# FrontEndEval.net
KiCad netlist of a schematic drawn in Altium Designer
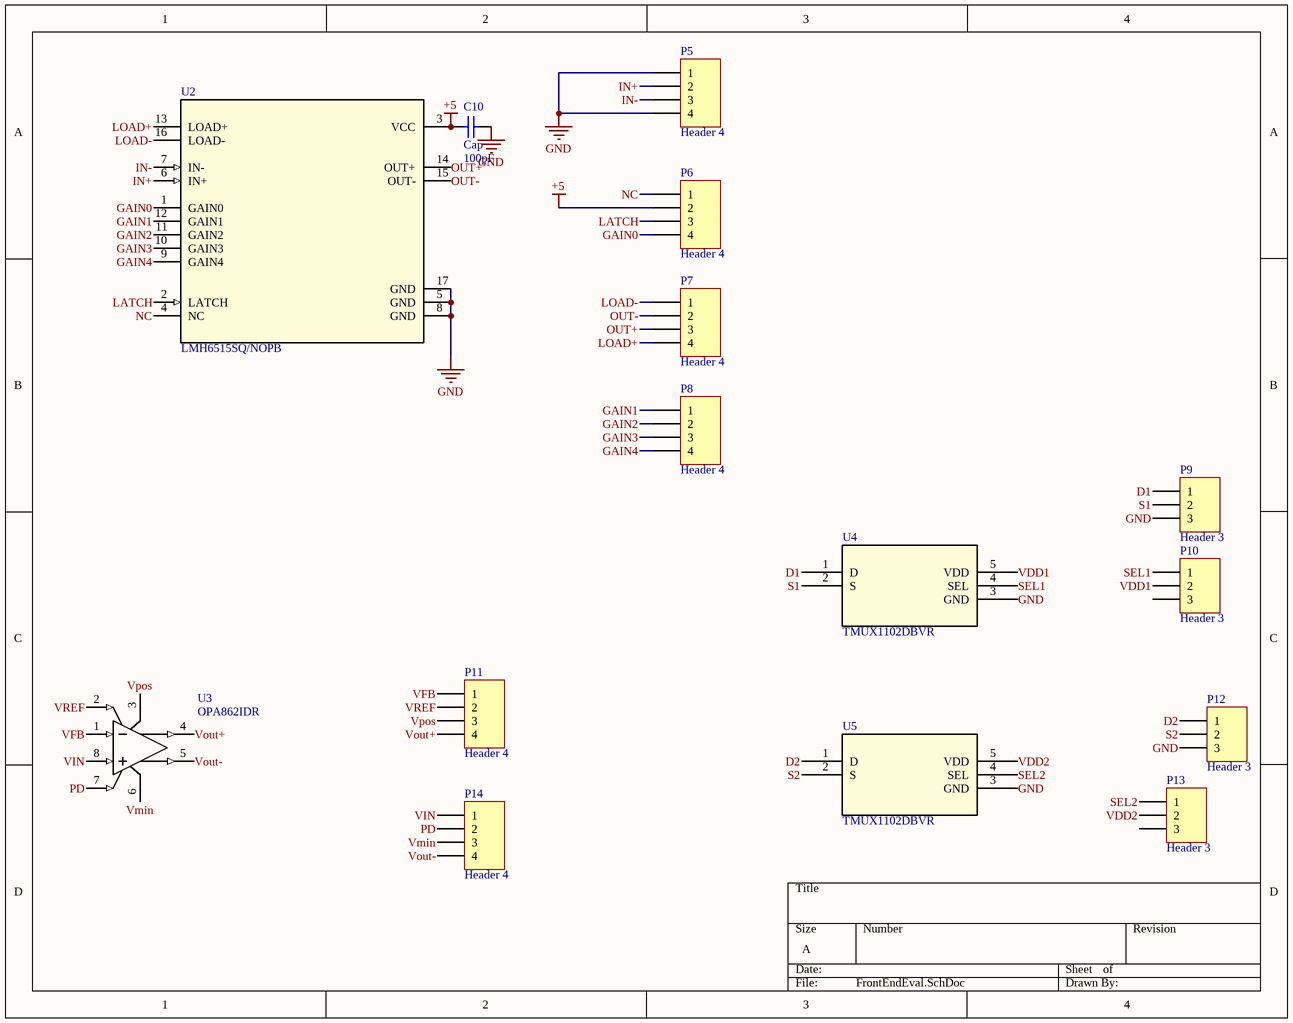
[diagram p0: FrontEndEval.SchDoc]

(export (version "E")
  (design (tool "Eeschema 10.0.6"))
  (components
    (comp (ref "C10")
      (value "Cap")
      (footprint "RAD-0.3")
      (description "Capacitor")
      (fields (field (name "ALTIUM_VALUE") "100pF") (field (name "PUBLISHER") "Altium Limited"))
      (libsource (lib "Miscellaneous Devices") (part "Cap"))
    )
    (comp (ref "P5")
      (value "Header 4")
      (footprint "HDR1X4")
      (description "Header, 4-Pin")
      (fields (field (name "PUBLISHER") "Altium Limited"))
      (libsource (lib "Miscellaneous Connectors") (part "Header 4"))
    )
    (comp (ref "P6")
      (value "Header 4")
      (footprint "HDR1X4")
      (description "Header, 4-Pin")
      (fields (field (name "PUBLISHER") "Altium Limited"))
      (libsource (lib "Miscellaneous Connectors") (part "Header 4"))
    )
    (comp (ref "P7")
      (value "Header 4")
      (footprint "HDR1X4")
      (description "Header, 4-Pin")
      (fields (field (name "PUBLISHER") "Altium Limited"))
      (libsource (lib "Miscellaneous Connectors") (part "Header 4"))
    )
    (comp (ref "P8")
      (value "Header 4")
      (footprint "HDR1X4")
      (description "Header, 4-Pin")
      (fields (field (name "PUBLISHER") "Altium Limited"))
      (libsource (lib "Miscellaneous Connectors") (part "Header 4"))
    )
    (comp (ref "P9")
      (value "Header 3")
      (footprint "HDR1X3")
      (description "Header, 3-Pin")
      (fields (field (name "PUBLISHER") "Altium Limited"))
      (libsource (lib "Miscellaneous Connectors") (part "Header 3"))
    )
    (comp (ref "P10")
      (value "Header 3")
      (footprint "HDR1X3")
      (description "Header, 3-Pin")
      (fields (field (name "PUBLISHER") "Altium Limited"))
      (libsource (lib "Miscellaneous Connectors") (part "Header 3"))
    )
    (comp (ref "P11")
      (value "Header 4")
      (footprint "HDR1X4")
      (description "Header, 4-Pin")
      (fields (field (name "PUBLISHER") "Altium Limited"))
      (libsource (lib "Miscellaneous Connectors") (part "Header 4"))
    )
    (comp (ref "P12")
      (value "Header 3")
      (footprint "HDR1X3")
      (description "Header, 3-Pin")
      (fields (field (name "PUBLISHER") "Altium Limited"))
      (libsource (lib "Miscellaneous Connectors") (part "Header 3"))
    )
    (comp (ref "P13")
      (value "Header 3")
      (footprint "HDR1X3")
      (description "Header, 3-Pin")
      (fields (field (name "PUBLISHER") "Altium Limited"))
      (libsource (lib "Miscellaneous Connectors") (part "Header 3"))
    )
    (comp (ref "P14")
      (value "Header 4")
      (footprint "HDR1X4")
      (description "Header, 4-Pin")
      (fields (field (name "PUBLISHER") "Altium Limited"))
      (libsource (lib "Miscellaneous Connectors") (part "Header 4"))
    )
    (comp (ref "U2")
      (value "LMH6515SQ/NOPB")
      (footprint "SQA16A")
      (description "No Description Available")
      (fields (field (name "COPYRIGHT") "Copyright (C) 2018 Accelerated Designs. All rights reserved"))
      (libsource (lib "LMH6515") (part "LMH6515SQ/NOPB"))
    )
    (comp (ref "U3")
      (value "OPA862IDR")
      (footprint "D0008A_N")
      (description "No Description Available")
      (fields
        (field (name "MANUFACTURER") "Texas Instruments")
        (field (name "COPYRIGHT") "Copyright (C) 2018 Accelerated Designs. All rights reserved")
      )
      (libsource (lib "OPA862") (part "OPA862IDR"))
    )
    (comp (ref "U4")
      (value "TMUX1102DBVR")
      (footprint "SOT-23-5_1P6X2P9_THT")
      (description "No Description Available")
      (fields (field (name "COPYRIGHT") "Copyright (C) 2018 Accelerated Designs. All rights reserved"))
      (libsource (lib "TMUX1102DBVR") (part "TMUX1102DBVR"))
    )
    (comp (ref "U5")
      (value "TMUX1102DBVR")
      (footprint "SOT-23-5_1P6X2P9_THT")
      (description "No Description Available")
      (fields (field (name "COPYRIGHT") "Copyright (C) 2018 Accelerated Designs. All rights reserved"))
      (libsource (lib "TMUX1102DBVR") (part "TMUX1102DBVR"))
    )
  )
  (nets
    (net (code "1") (name "+5") (class "Default")
      (node (ref "C10") (pin "1") (pinfunction "1_1") (pintype "passive"))
      (node (ref "P6") (pin "2") (pinfunction "2_2") (pintype "passive"))
      (node (ref "U2") (pin "3") (pinfunction "VCC_3") (pintype "power_in"))
    )
    (net (code "2") (name "/D1") (class "Default")
      (node (ref "P9") (pin "1") (pinfunction "1_1") (pintype "passive"))
      (node (ref "U4") (pin "1") (pinfunction "D_1") (pintype "passive"))
    )
    (net (code "3") (name "/D2") (class "Default")
      (node (ref "P12") (pin "1") (pinfunction "1_1") (pintype "passive"))
      (node (ref "U5") (pin "1") (pinfunction "D_1") (pintype "passive"))
    )
    (net (code "4") (name "/GAIN0") (class "Default")
      (node (ref "P6") (pin "4") (pinfunction "4_4") (pintype "passive"))
      (node (ref "U2") (pin "1") (pinfunction "GAIN0_1") (pintype "passive"))
    )
    (net (code "5") (name "/GAIN1") (class "Default")
      (node (ref "P8") (pin "1") (pinfunction "1_1") (pintype "passive"))
      (node (ref "U2") (pin "12") (pinfunction "GAIN1_12") (pintype "passive"))
    )
    (net (code "6") (name "/GAIN2") (class "Default")
      (node (ref "P8") (pin "2") (pinfunction "2_2") (pintype "passive"))
      (node (ref "U2") (pin "11") (pinfunction "GAIN2_11") (pintype "passive"))
    )
    (net (code "7") (name "/GAIN3") (class "Default")
      (node (ref "P8") (pin "3") (pinfunction "3_3") (pintype "passive"))
      (node (ref "U2") (pin "10") (pinfunction "GAIN3_10") (pintype "passive"))
    )
    (net (code "8") (name "/GAIN4") (class "Default")
      (node (ref "P8") (pin "4") (pinfunction "4_4") (pintype "passive"))
      (node (ref "U2") (pin "9") (pinfunction "GAIN4_9") (pintype "passive"))
    )
    (net (code "9") (name "/IN+") (class "Default")
      (node (ref "P5") (pin "2") (pinfunction "2_2") (pintype "passive"))
      (node (ref "U2") (pin "6") (pinfunction "IN+_6") (pintype "input"))
    )
    (net (code "10") (name "/IN-") (class "Default")
      (node (ref "P5") (pin "3") (pinfunction "3_3") (pintype "passive"))
      (node (ref "U2") (pin "7") (pinfunction "IN-_7") (pintype "input"))
    )
    (net (code "11") (name "/LATCH") (class "Default")
      (node (ref "P6") (pin "3") (pinfunction "3_3") (pintype "passive"))
      (node (ref "U2") (pin "2") (pinfunction "LATCH_2") (pintype "input"))
    )
    (net (code "12") (name "/LOAD+") (class "Default")
      (node (ref "P7") (pin "4") (pinfunction "4_4") (pintype "passive"))
      (node (ref "U2") (pin "13") (pinfunction "LOAD+_13") (pintype "passive"))
    )
    (net (code "13") (name "/LOAD-") (class "Default")
      (node (ref "P7") (pin "1") (pinfunction "1_1") (pintype "passive"))
      (node (ref "U2") (pin "16") (pinfunction "LOAD-_16") (pintype "passive"))
    )
    (net (code "14") (name "/NC") (class "Default")
      (node (ref "P6") (pin "1") (pinfunction "1_1") (pintype "passive"))
      (node (ref "U2") (pin "4") (pinfunction "NC_4") (pintype "passive"))
    )
    (net (code "15") (name "/OUT+") (class "Default")
      (node (ref "P7") (pin "3") (pinfunction "3_3") (pintype "passive"))
      (node (ref "U2") (pin "14") (pinfunction "OUT+_14") (pintype "passive"))
    )
    (net (code "16") (name "/OUT-") (class "Default")
      (node (ref "P7") (pin "2") (pinfunction "2_2") (pintype "passive"))
      (node (ref "U2") (pin "15") (pinfunction "OUT-_15") (pintype "passive"))
    )
    (net (code "17") (name "/PD") (class "Default")
      (node (ref "P14") (pin "2") (pinfunction "2_2") (pintype "passive"))
      (node (ref "U3") (pin "7") (pinfunction "PD_N_7") (pintype "input"))
    )
    (net (code "18") (name "/S1") (class "Default")
      (node (ref "P9") (pin "2") (pinfunction "2_2") (pintype "passive"))
      (node (ref "U4") (pin "2") (pinfunction "S_2") (pintype "passive"))
    )
    (net (code "19") (name "/S2") (class "Default")
      (node (ref "P12") (pin "2") (pinfunction "2_2") (pintype "passive"))
      (node (ref "U5") (pin "2") (pinfunction "S_2") (pintype "passive"))
    )
    (net (code "20") (name "/SEL1") (class "Default")
      (node (ref "P10") (pin "1") (pinfunction "1_1") (pintype "passive"))
      (node (ref "U4") (pin "4") (pinfunction "SEL_4") (pintype "passive"))
    )
    (net (code "21") (name "/SEL2") (class "Default")
      (node (ref "P13") (pin "1") (pinfunction "1_1") (pintype "passive"))
      (node (ref "U5") (pin "4") (pinfunction "SEL_4") (pintype "passive"))
    )
    (net (code "22") (name "/VDD1") (class "Default")
      (node (ref "P10") (pin "2") (pinfunction "2_2") (pintype "passive"))
      (node (ref "U4") (pin "5") (pinfunction "VDD_5") (pintype "power_in"))
    )
    (net (code "23") (name "/VDD2") (class "Default")
      (node (ref "P13") (pin "2") (pinfunction "2_2") (pintype "passive"))
      (node (ref "U5") (pin "5") (pinfunction "VDD_5") (pintype "power_in"))
    )
    (net (code "24") (name "/VFB") (class "Default")
      (node (ref "P11") (pin "1") (pinfunction "1_1") (pintype "passive"))
      (node (ref "U3") (pin "1") (pinfunction "VIN-_1") (pintype "input"))
    )
    (net (code "25") (name "/VIN") (class "Default")
      (node (ref "P14") (pin "1") (pinfunction "1_1") (pintype "passive"))
      (node (ref "U3") (pin "8") (pinfunction "VIN+_8") (pintype "input"))
    )
    (net (code "26") (name "/VREF") (class "Default")
      (node (ref "P11") (pin "2") (pinfunction "2_2") (pintype "passive"))
      (node (ref "U3") (pin "2") (pinfunction "VOCM_2") (pintype "input"))
    )
    (net (code "27") (name "/Vmin") (class "Default")
      (node (ref "P14") (pin "3") (pinfunction "3_3") (pintype "passive"))
      (node (ref "U3") (pin "6") (pinfunction "VS-_6") (pintype "power_in"))
    )
    (net (code "28") (name "/Vout+") (class "Default")
      (node (ref "P11") (pin "4") (pinfunction "4_4") (pintype "passive"))
      (node (ref "U3") (pin "4") (pinfunction "VOUT+_4") (pintype "output"))
    )
    (net (code "29") (name "/Vout-") (class "Default")
      (node (ref "P14") (pin "4") (pinfunction "4_4") (pintype "passive"))
      (node (ref "U3") (pin "5") (pinfunction "VOUT-_5") (pintype "output"))
    )
    (net (code "30") (name "/Vpos") (class "Default")
      (node (ref "P11") (pin "3") (pinfunction "3_3") (pintype "passive"))
      (node (ref "U3") (pin "3") (pinfunction "VS+_3") (pintype "power_in"))
    )
    (net (code "31") (name "GND") (class "Default")
      (node (ref "C10") (pin "2") (pinfunction "2_2") (pintype "passive"))
      (node (ref "P12") (pin "3") (pinfunction "3_3") (pintype "passive"))
      (node (ref "P5") (pin "1") (pinfunction "1_1") (pintype "passive"))
      (node (ref "P5") (pin "4") (pinfunction "4_4") (pintype "passive"))
      (node (ref "P9") (pin "3") (pinfunction "3_3") (pintype "passive"))
      (node (ref "U2") (pin "17") (pinfunction "GND_17") (pintype "power_in"))
      (node (ref "U2") (pin "5") (pinfunction "GND_5") (pintype "power_in"))
      (node (ref "U2") (pin "8") (pinfunction "GND_8") (pintype "power_in"))
      (node (ref "U4") (pin "3") (pinfunction "GND_3") (pintype "passive"))
      (node (ref "U5") (pin "3") (pinfunction "GND_3") (pintype "passive"))
    )
    (net (code "32") (name "unconnected-(P10-Pad3)") (class "Default")
      (node (ref "P10") (pin "3") (pinfunction "3_3") (pintype "passive"))
    )
    (net (code "33") (name "unconnected-(P13-Pad3)") (class "Default")
      (node (ref "P13") (pin "3") (pinfunction "3_3") (pintype "passive"))
    )
  )
)
